# zero_board.net
KiCad netlist of a schematic drawn in EAGLE
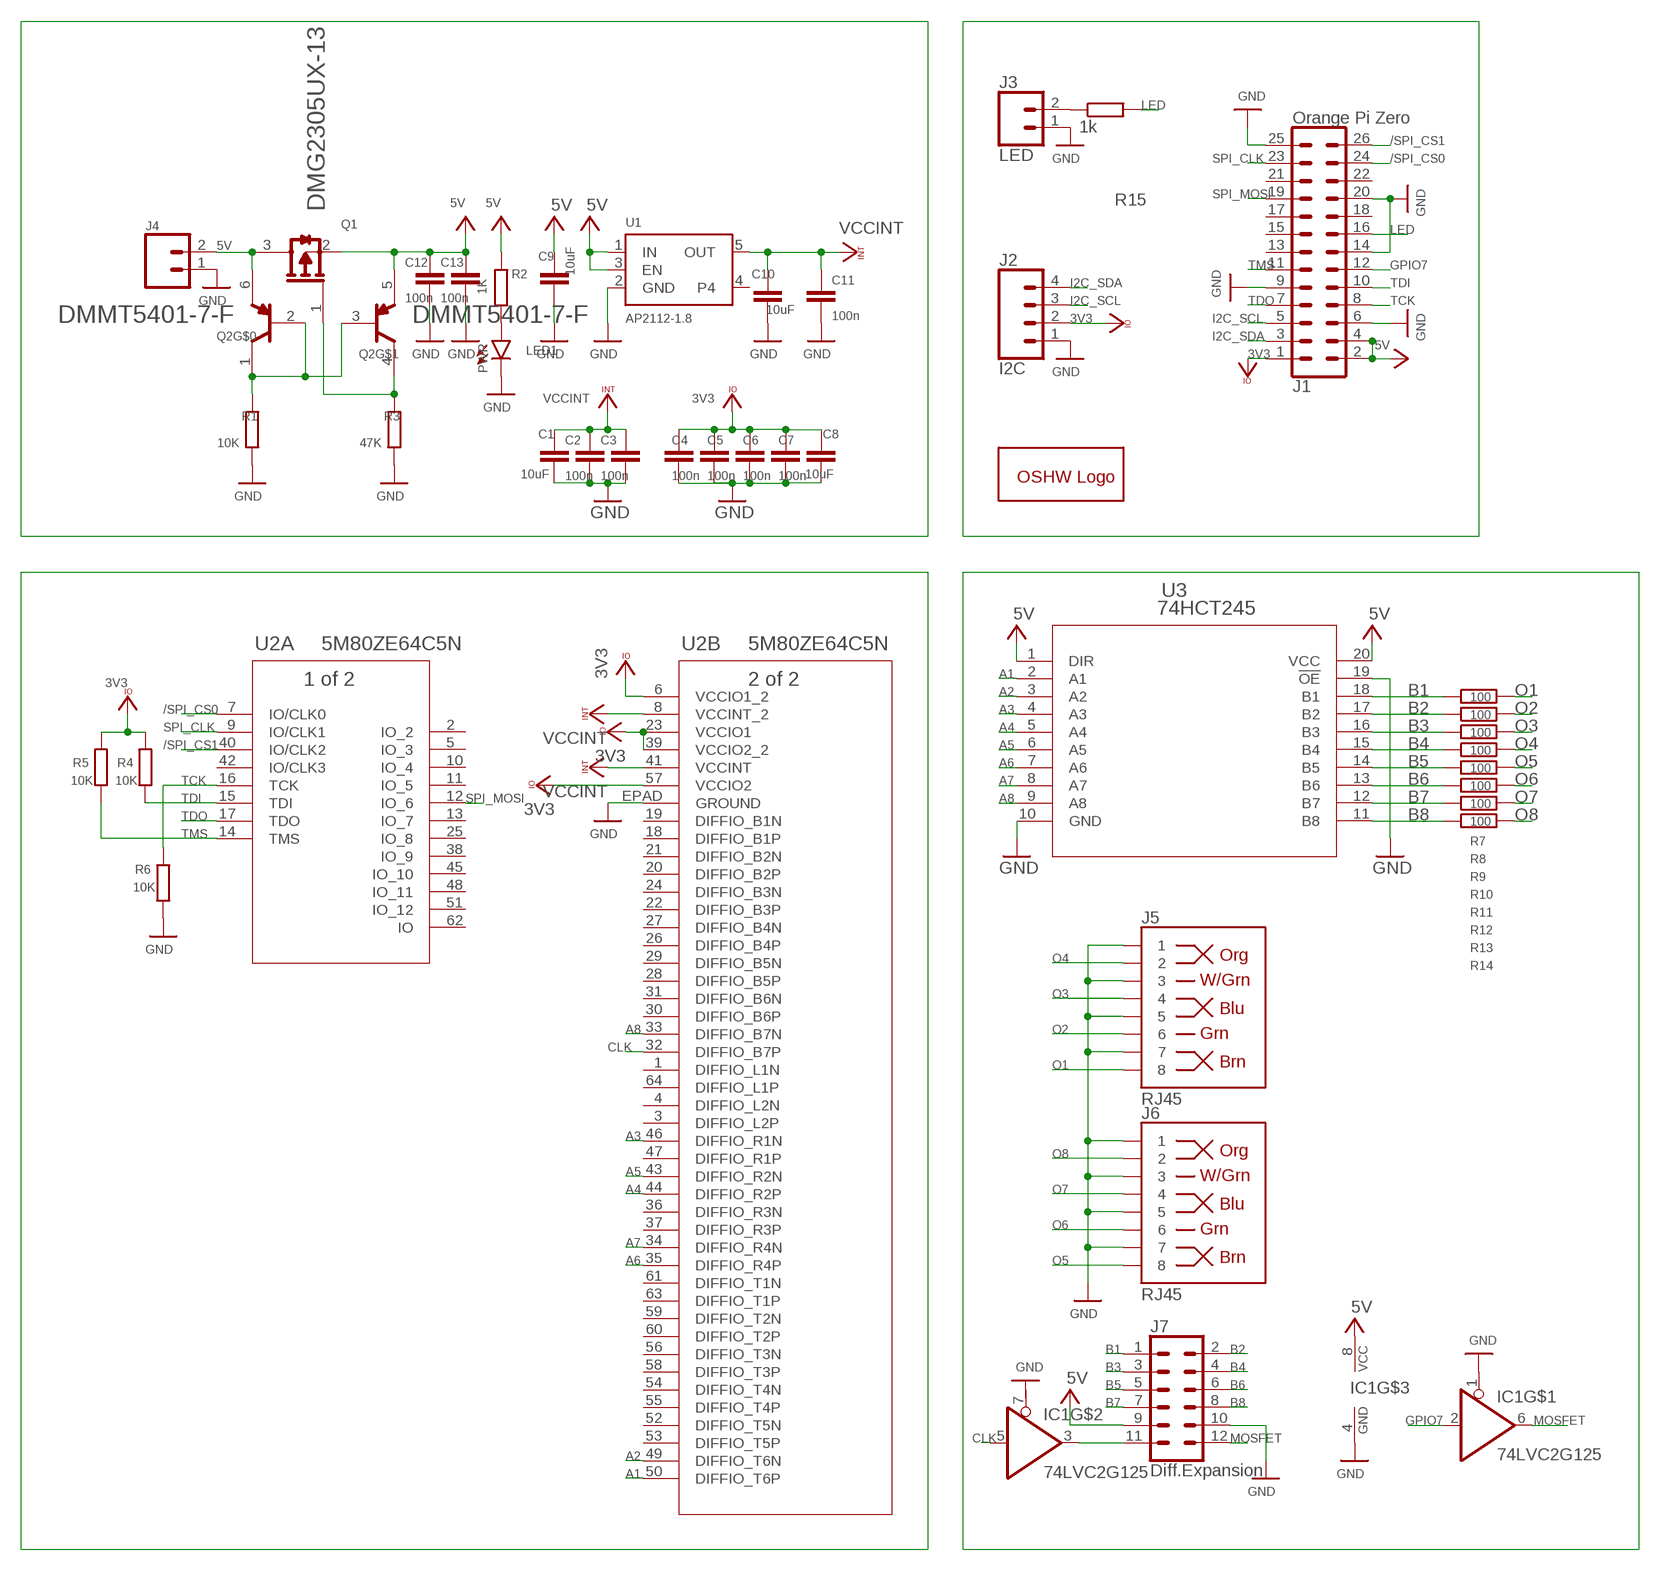
[diagram p0: schematic, sheet 1]

(export (version "E")
  (design (tool "Eeschema 10.0.6"))
  (components
    (comp (ref "C1")
      (value "10uF")
      (footprint "eagle-import:C0805")
      (libsource (lib "eagle-import") (part "C-EUC0805"))
    )
    (comp (ref "C2")
      (value "100n")
      (footprint "eagle-import:C0603")
      (libsource (lib "eagle-import") (part "C-EUC0603"))
    )
    (comp (ref "C3")
      (value "100n")
      (footprint "eagle-import:C0603")
      (libsource (lib "eagle-import") (part "C-EUC0603"))
    )
    (comp (ref "C4")
      (value "100n")
      (footprint "eagle-import:C0603")
      (libsource (lib "eagle-import") (part "C-EUC0603"))
    )
    (comp (ref "C5")
      (value "100n")
      (footprint "eagle-import:C0603")
      (libsource (lib "eagle-import") (part "C-EUC0603"))
    )
    (comp (ref "C6")
      (value "100n")
      (footprint "eagle-import:C0603")
      (libsource (lib "eagle-import") (part "C-EUC0603"))
    )
    (comp (ref "C7")
      (value "100n")
      (footprint "eagle-import:C0603")
      (libsource (lib "eagle-import") (part "C-EUC0603"))
    )
    (comp (ref "C8")
      (value "10uF")
      (footprint "eagle-import:C0805")
      (libsource (lib "eagle-import") (part "C-EUC0805"))
    )
    (comp (ref "C9")
      (value "10uF")
      (footprint "eagle-import:C0805")
      (libsource (lib "eagle-import") (part "C-EUC0805"))
    )
    (comp (ref "C10")
      (value "10uF")
      (footprint "eagle-import:C0805")
      (libsource (lib "eagle-import") (part "C-EUC0805"))
    )
    (comp (ref "C11")
      (value "100n")
      (footprint "eagle-import:C0603")
      (libsource (lib "eagle-import") (part "C-EUC0603"))
    )
    (comp (ref "C12")
      (value "100n")
      (footprint "eagle-import:C0603")
      (libsource (lib "eagle-import") (part "C-EUC0603"))
    )
    (comp (ref "C13")
      (value "100n")
      (footprint "eagle-import:C0603")
      (libsource (lib "eagle-import") (part "C-EUC0603"))
    )
    (comp (ref "GOLD_ORB_SM1")
      (value "OSHWLOGOLOGO5MM")
      (footprint "eagle-import:OSHW_5MM")
      (libsource (lib "eagle-import") (part "OSHWLOGOLOGO5MM"))
    )
    (comp (ref "IC1")
      (value "74LVC2G125")
      (footprint "eagle-import:SSOP08")
      (libsource (lib "eagle-import") (part "742G125DCTLVC"))
    )
    (comp (ref "J1")
      (value "Orange Pi Zero")
      (footprint "eagle-import:2X13")
      (libsource (lib "eagle-import") (part "CONN_13X22X13"))
    )
    (comp (ref "J2")
      (value "I2C")
      (footprint "eagle-import:1X04")
      (libsource (lib "eagle-import") (part "CONN_04"))
    )
    (comp (ref "J3")
      (value "LED")
      (footprint "eagle-import:1X02")
      (libsource (lib "eagle-import") (part "SparkFun-Connectors_513_CONN_02"))
    )
    (comp (ref "J4")
      (value "5V")
      (footprint "eagle-import:SCREWTERMINAL-3.5MM-2")
      (libsource (lib "eagle-import") (part "CONN_023.5MM"))
    )
    (comp (ref "J5")
      (value "RJ45")
      (footprint "eagle-import:RJ45-8")
      (libsource (lib "eagle-import") (part "RJ45-8"))
    )
    (comp (ref "J6")
      (value "RJ45")
      (footprint "eagle-import:RJ45-8")
      (libsource (lib "eagle-import") (part "RJ45-8"))
    )
    (comp (ref "J7")
      (value "Diff.Expansion")
      (footprint "eagle-import:2X6")
      (libsource (lib "eagle-import") (part "CONN_06X2PTH_FEMALE"))
    )
    (comp (ref "LED1")
      (value "PWR")
      (footprint "eagle-import:CHIP-LED0603")
      (libsource (lib "eagle-import") (part "LEDCHIP-LED0603"))
    )
    (comp (ref "Q1")
      (value "DIODES_INC._DMG2305UX-13DIODES_INC._DMG2305UX-13_0_0")
      (footprint "eagle-import:DIODES_INC._DMG2305UX-13_0")
      (fields
        (field (name "DIGIKEY_PART_NUMBER") "DMG2305UX-13DICT-ND")
        (field (name "MF") "Diodes Inc.")
        (field (name "MOUSER_PART_NUMBER") "621-DMG2305UX-13")
      )
      (libsource (lib "eagle-import") (part "DIODES_INC._DMG2305UX-13DIODES_INC._DMG2305UX-13_0_0"))
    )
    (comp (ref "Q2")
      (value "DMMT5401-7-F_0_0")
      (footprint "eagle-import:DIODES_DMMT5401-7-F_0")
      (fields
        (field (name "DIGIKEY_PART_NUMBER") "DMMT5401-FDICT-ND")
        (field (name "MF") "Diodes")
        (field (name "MOUSER_PART_NUMBER") "621-DMMT5401-7-F")
      )
      (libsource (lib "eagle-import") (part "DIODES_DMMT5401-7-FDIODES_DMMT5401-7-F_0_0"))
    )
    (comp (ref "R1")
      (value "10K")
      (footprint "eagle-import:R0402")
      (libsource (lib "eagle-import") (part "R-EU_R0402"))
    )
    (comp (ref "R2")
      (value "1K")
      (footprint "eagle-import:R0402")
      (libsource (lib "eagle-import") (part "resistor_348_R-EU_R0402"))
    )
    (comp (ref "R3")
      (value "47K")
      (footprint "eagle-import:R0402")
      (libsource (lib "eagle-import") (part "R-EU_R0402"))
    )
    (comp (ref "R4")
      (value "10K")
      (footprint "eagle-import:R0402")
      (libsource (lib "eagle-import") (part "R-EU_R0402"))
    )
    (comp (ref "R5")
      (value "10K")
      (footprint "eagle-import:R0402")
      (libsource (lib "eagle-import") (part "R-EU_R0402"))
    )
    (comp (ref "R6")
      (value "10K")
      (footprint "eagle-import:R0402")
      (libsource (lib "eagle-import") (part "R-EU_R0402"))
    )
    (comp (ref "R7")
      (value "100")
      (footprint "eagle-import:R0402")
      (libsource (lib "eagle-import") (part "R-EU_R0402"))
    )
    (comp (ref "R8")
      (value "100")
      (footprint "eagle-import:R0402")
      (libsource (lib "eagle-import") (part "R-EU_R0402"))
    )
    (comp (ref "R9")
      (value "100")
      (footprint "eagle-import:R0402")
      (libsource (lib "eagle-import") (part "R-EU_R0402"))
    )
    (comp (ref "R10")
      (value "100")
      (footprint "eagle-import:R0402")
      (libsource (lib "eagle-import") (part "R-EU_R0402"))
    )
    (comp (ref "R11")
      (value "100")
      (footprint "eagle-import:R0402")
      (libsource (lib "eagle-import") (part "R-EU_R0402"))
    )
    (comp (ref "R12")
      (value "100")
      (footprint "eagle-import:R0402")
      (libsource (lib "eagle-import") (part "R-EU_R0402"))
    )
    (comp (ref "R13")
      (value "100")
      (footprint "eagle-import:R0402")
      (libsource (lib "eagle-import") (part "R-EU_R0402"))
    )
    (comp (ref "R14")
      (value "100")
      (footprint "eagle-import:R0402")
      (libsource (lib "eagle-import") (part "R-EU_R0402"))
    )
    (comp (ref "R15")
      (value "1k")
      (footprint "eagle-import:R0402")
      (libsource (lib "eagle-import") (part "R-EU_R0402"))
    )
    (comp (ref "U1")
      (value "AP2112-1.8")
      (footprint "eagle-import:SOT23-5")
      (libsource (lib "eagle-import") (part "VREG_SOT23-5"))
    )
    (comp (ref "U2")
      (value "5M80ZE64C5N")
      (footprint "eagle-import:EQFP64P_A1P2-D4P5_INT-L")
      (fields (field (name "COPYRIGHT") "Copyright (C) 2018 Accelerated Designs. All rights reserved"))
      (libsource (lib "eagle-import") (part "5M80ZE64C5NEQFP64P_A1P2-D4P5_INT-L"))
    )
    (comp (ref "U3")
      (value "74HCT245")
      (footprint "eagle-import:PW20")
      (fields
        (field (name "GENERIC_PART_NUMBER") "SN74HCT245")
        (field (name "MANUFACTURER") "Texas Instruments")
        (field (name "MANUFACTURER_PART_NUMBER") "SN74HCT245PWR")
      )
      (libsource (lib "eagle-import") (part "SN74HCT245PWR"))
    )
  )
  (nets
    (net (code "1") (name "/A1") (class "Default")
      (node (ref "U2") (pin "50") (pinfunction "DIFFIO_T6P_50") (pintype "bidirectional"))
      (node (ref "U3") (pin "2") (pinfunction "A1_2") (pintype "bidirectional"))
    )
    (net (code "2") (name "/A2") (class "Default")
      (node (ref "U2") (pin "49") (pinfunction "DIFFIO_T6N_49") (pintype "bidirectional"))
      (node (ref "U3") (pin "3") (pinfunction "A2_3") (pintype "bidirectional"))
    )
    (net (code "3") (name "/A3") (class "Default")
      (node (ref "U2") (pin "46") (pinfunction "DIFFIO_R1N_46") (pintype "bidirectional"))
      (node (ref "U3") (pin "4") (pinfunction "A3_4") (pintype "bidirectional"))
    )
    (net (code "4") (name "/A4") (class "Default")
      (node (ref "U2") (pin "44") (pinfunction "DIFFIO_R2P_44") (pintype "bidirectional"))
      (node (ref "U3") (pin "5") (pinfunction "A4_5") (pintype "bidirectional"))
    )
    (net (code "5") (name "/A5") (class "Default")
      (node (ref "U2") (pin "43") (pinfunction "DIFFIO_R2N_43") (pintype "bidirectional"))
      (node (ref "U3") (pin "6") (pinfunction "A5_6") (pintype "bidirectional"))
    )
    (net (code "6") (name "/A6") (class "Default")
      (node (ref "U2") (pin "35") (pinfunction "DIFFIO_R4P_35") (pintype "bidirectional"))
      (node (ref "U3") (pin "7") (pinfunction "A6_7") (pintype "bidirectional"))
    )
    (net (code "7") (name "/A7") (class "Default")
      (node (ref "U2") (pin "34") (pinfunction "DIFFIO_R4N_34") (pintype "bidirectional"))
      (node (ref "U3") (pin "8") (pinfunction "A7_8") (pintype "bidirectional"))
    )
    (net (code "8") (name "/A8") (class "Default")
      (node (ref "U2") (pin "33") (pinfunction "DIFFIO_B7N_33") (pintype "bidirectional"))
      (node (ref "U3") (pin "9") (pinfunction "A8_9") (pintype "bidirectional"))
    )
    (net (code "9") (name "/B1") (class "Default")
      (node (ref "J7") (pin "1") (pinfunction "1_1") (pintype "passive"))
      (node (ref "R7") (pin "1") (pinfunction "1_1") (pintype "passive"))
      (node (ref "U3") (pin "18") (pinfunction "B1_18") (pintype "bidirectional"))
    )
    (net (code "10") (name "/B2") (class "Default")
      (node (ref "J7") (pin "2") (pinfunction "2_2") (pintype "passive"))
      (node (ref "R8") (pin "1") (pinfunction "1_1") (pintype "passive"))
      (node (ref "U3") (pin "17") (pinfunction "B2_17") (pintype "bidirectional"))
    )
    (net (code "11") (name "/B3") (class "Default")
      (node (ref "J7") (pin "3") (pinfunction "3_3") (pintype "passive"))
      (node (ref "R9") (pin "1") (pinfunction "1_1") (pintype "passive"))
      (node (ref "U3") (pin "16") (pinfunction "B3_16") (pintype "bidirectional"))
    )
    (net (code "12") (name "/B4") (class "Default")
      (node (ref "J7") (pin "4") (pinfunction "4_4") (pintype "passive"))
      (node (ref "R10") (pin "1") (pinfunction "1_1") (pintype "passive"))
      (node (ref "U3") (pin "15") (pinfunction "B4_15") (pintype "bidirectional"))
    )
    (net (code "13") (name "/B5") (class "Default")
      (node (ref "J7") (pin "5") (pinfunction "5_5") (pintype "passive"))
      (node (ref "R11") (pin "1") (pinfunction "1_1") (pintype "passive"))
      (node (ref "U3") (pin "14") (pinfunction "B5_14") (pintype "bidirectional"))
    )
    (net (code "14") (name "/B6") (class "Default")
      (node (ref "J7") (pin "6") (pinfunction "6_6") (pintype "passive"))
      (node (ref "R12") (pin "1") (pinfunction "1_1") (pintype "passive"))
      (node (ref "U3") (pin "13") (pinfunction "B6_13") (pintype "bidirectional"))
    )
    (net (code "15") (name "/B7") (class "Default")
      (node (ref "J7") (pin "7") (pinfunction "7_7") (pintype "passive"))
      (node (ref "R13") (pin "1") (pinfunction "1_1") (pintype "passive"))
      (node (ref "U3") (pin "12") (pinfunction "B7_12") (pintype "bidirectional"))
    )
    (net (code "16") (name "/B8") (class "Default")
      (node (ref "J7") (pin "8") (pinfunction "8_8") (pintype "passive"))
      (node (ref "R14") (pin "1") (pinfunction "1_1") (pintype "passive"))
      (node (ref "U3") (pin "11") (pinfunction "B8_11") (pintype "bidirectional"))
    )
    (net (code "17") (name "/CLK") (class "Default")
      (node (ref "IC1") (pin "5") (pinfunction "I_5") (pintype "input"))
      (node (ref "U2") (pin "32") (pinfunction "DIFFIO_B7P_32") (pintype "bidirectional"))
    )
    (net (code "18") (name "/GPIO7") (class "Default")
      (node (ref "IC1") (pin "2") (pinfunction "I_2") (pintype "input"))
      (node (ref "J1") (pin "12") (pinfunction "12_12") (pintype "passive"))
    )
    (net (code "19") (name "/I2C_SCL") (class "Default")
      (node (ref "J1") (pin "5") (pinfunction "5_5") (pintype "passive"))
      (node (ref "J2") (pin "3") (pinfunction "3_3") (pintype "passive"))
    )
    (net (code "20") (name "/I2C_SDA") (class "Default")
      (node (ref "J1") (pin "3") (pinfunction "3_3") (pintype "passive"))
      (node (ref "J2") (pin "4") (pinfunction "4_4") (pintype "passive"))
    )
    (net (code "21") (name "/LED") (class "Default")
      (node (ref "J1") (pin "16") (pinfunction "16_16") (pintype "passive"))
      (node (ref "R15") (pin "2") (pinfunction "2_2") (pintype "passive"))
    )
    (net (code "22") (name "/MOSFET") (class "Default")
      (node (ref "IC1") (pin "6") (pinfunction "O_6") (pintype "tri_state"))
      (node (ref "J7") (pin "12") (pinfunction "12_12") (pintype "passive"))
    )
    (net (code "23") (name "/O1") (class "Default")
      (node (ref "J5") (pin "8") (pinfunction "8_8") (pintype "bidirectional"))
      (node (ref "R7") (pin "2") (pinfunction "2_2") (pintype "passive"))
    )
    (net (code "24") (name "/O2") (class "Default")
      (node (ref "J5") (pin "6") (pinfunction "6_6") (pintype "bidirectional"))
      (node (ref "R8") (pin "2") (pinfunction "2_2") (pintype "passive"))
    )
    (net (code "25") (name "/O3") (class "Default")
      (node (ref "J5") (pin "4") (pinfunction "4_4") (pintype "bidirectional"))
      (node (ref "R9") (pin "2") (pinfunction "2_2") (pintype "passive"))
    )
    (net (code "26") (name "/O4") (class "Default")
      (node (ref "J5") (pin "2") (pinfunction "2_2") (pintype "bidirectional"))
      (node (ref "R10") (pin "2") (pinfunction "2_2") (pintype "passive"))
    )
    (net (code "27") (name "/O5") (class "Default")
      (node (ref "J6") (pin "8") (pinfunction "8_8") (pintype "bidirectional"))
      (node (ref "R11") (pin "2") (pinfunction "2_2") (pintype "passive"))
    )
    (net (code "28") (name "/O6") (class "Default")
      (node (ref "J6") (pin "6") (pinfunction "6_6") (pintype "bidirectional"))
      (node (ref "R12") (pin "2") (pinfunction "2_2") (pintype "passive"))
    )
    (net (code "29") (name "/O7") (class "Default")
      (node (ref "J6") (pin "4") (pinfunction "4_4") (pintype "bidirectional"))
      (node (ref "R13") (pin "2") (pinfunction "2_2") (pintype "passive"))
    )
    (net (code "30") (name "/O8") (class "Default")
      (node (ref "J6") (pin "2") (pinfunction "2_2") (pintype "bidirectional"))
      (node (ref "R14") (pin "2") (pinfunction "2_2") (pintype "passive"))
    )
    (net (code "31") (name "/SPI_CLK") (class "Default")
      (node (ref "J1") (pin "23") (pinfunction "23_23") (pintype "passive"))
      (node (ref "U2") (pin "9") (pinfunction "IO/CLK1_9") (pintype "bidirectional"))
    )
    (net (code "32") (name "/SPI_MOSI") (class "Default")
      (node (ref "J1") (pin "19") (pinfunction "19_19") (pintype "passive"))
      (node (ref "U2") (pin "12") (pinfunction "IO_6_12") (pintype "bidirectional"))
    )
    (net (code "33") (name "/TCK") (class "Default")
      (node (ref "J1") (pin "8") (pinfunction "8_8") (pintype "passive"))
      (node (ref "R6") (pin "2") (pinfunction "2_2") (pintype "passive"))
      (node (ref "U2") (pin "16") (pinfunction "TCK_16") (pintype "passive"))
    )
    (net (code "34") (name "/TDI") (class "Default")
      (node (ref "J1") (pin "10") (pinfunction "10_10") (pintype "passive"))
      (node (ref "R4") (pin "1") (pinfunction "1_1") (pintype "passive"))
      (node (ref "U2") (pin "15") (pinfunction "TDI_15") (pintype "passive"))
    )
    (net (code "35") (name "/TDO") (class "Default")
      (node (ref "J1") (pin "7") (pinfunction "7_7") (pintype "passive"))
      (node (ref "U2") (pin "17") (pinfunction "TDO_17") (pintype "passive"))
    )
    (net (code "36") (name "/TMS") (class "Default")
      (node (ref "J1") (pin "11") (pinfunction "11_11") (pintype "passive"))
      (node (ref "R5") (pin "1") (pinfunction "1_1") (pintype "passive"))
      (node (ref "U2") (pin "14") (pinfunction "TMS_14") (pintype "passive"))
    )
    (net (code "37") (name "/{slash}SPI_CS0") (class "Default")
      (node (ref "J1") (pin "24") (pinfunction "24_24") (pintype "passive"))
      (node (ref "U2") (pin "7") (pinfunction "IO/CLK0_7") (pintype "bidirectional"))
    )
    (net (code "38") (name "/{slash}SPI_CS1") (class "Default")
      (node (ref "J1") (pin "26") (pinfunction "26_26") (pintype "passive"))
      (node (ref "U2") (pin "40") (pinfunction "IO/CLK2_40") (pintype "bidirectional"))
    )
    (net (code "39") (name "3V3") (class "Default")
      (node (ref "C4") (pin "1") (pinfunction "1_1") (pintype "passive"))
      (node (ref "C5") (pin "1") (pinfunction "1_1") (pintype "passive"))
      (node (ref "C6") (pin "1") (pinfunction "1_1") (pintype "passive"))
      (node (ref "C7") (pin "1") (pinfunction "1_1") (pintype "passive"))
      (node (ref "C8") (pin "1") (pinfunction "1_1") (pintype "passive"))
      (node (ref "J1") (pin "1") (pinfunction "1_1") (pintype "passive"))
      (node (ref "J2") (pin "2") (pinfunction "2_2") (pintype "passive"))
      (node (ref "R4") (pin "2") (pinfunction "2_2") (pintype "passive"))
      (node (ref "R5") (pin "2") (pinfunction "2_2") (pintype "passive"))
      (node (ref "U2") (pin "23") (pinfunction "VCCIO1_23") (pintype "power_in"))
      (node (ref "U2") (pin "39") (pinfunction "VCCIO2_2_39") (pintype "power_in"))
      (node (ref "U2") (pin "57") (pinfunction "VCCIO2_57") (pintype "power_in"))
      (node (ref "U2") (pin "6") (pinfunction "VCCIO1_2_6") (pintype "power_in"))
    )
    (net (code "40") (name "5V") (class "Default")
      (node (ref "C12") (pin "1") (pinfunction "1_1") (pintype "passive"))
      (node (ref "C13") (pin "1") (pinfunction "1_1") (pintype "passive"))
      (node (ref "C9") (pin "1") (pinfunction "1_1") (pintype "passive"))
      (node (ref "IC1") (pin "8") (pinfunction "VCC_8") (pintype "power_in"))
      (node (ref "J1") (pin "2") (pinfunction "2_2") (pintype "passive"))
      (node (ref "J1") (pin "4") (pinfunction "4_4") (pintype "passive"))
      (node (ref "J7") (pin "9") (pinfunction "9_9") (pintype "passive"))
      (node (ref "Q1") (pin "2") (pinfunction "S_2") (pintype "passive"))
      (node (ref "Q2") (pin "5") (pinfunction "E2_5") (pintype "passive"))
      (node (ref "R2") (pin "1") (pinfunction "1_1") (pintype "passive"))
      (node (ref "U1") (pin "1") (pinfunction "IN_1") (pintype "power_in"))
      (node (ref "U1") (pin "3") (pinfunction "EN_3") (pintype "input"))
      (node (ref "U3") (pin "1") (pinfunction "DIR_1") (pintype "input"))
      (node (ref "U3") (pin "20") (pinfunction "VCC_20") (pintype "power_in"))
    )
    (net (code "41") (name "GND") (class "Default")
      (node (ref "C1") (pin "2") (pinfunction "2_2") (pintype "passive"))
      (node (ref "C10") (pin "2") (pinfunction "2_2") (pintype "passive"))
      (node (ref "C11") (pin "2") (pinfunction "2_2") (pintype "passive"))
      (node (ref "C12") (pin "2") (pinfunction "2_2") (pintype "passive"))
      (node (ref "C13") (pin "2") (pinfunction "2_2") (pintype "passive"))
      (node (ref "C2") (pin "2") (pinfunction "2_2") (pintype "passive"))
      (node (ref "C3") (pin "2") (pinfunction "2_2") (pintype "passive"))
      (node (ref "C4") (pin "2") (pinfunction "2_2") (pintype "passive"))
      (node (ref "C5") (pin "2") (pinfunction "2_2") (pintype "passive"))
      (node (ref "C6") (pin "2") (pinfunction "2_2") (pintype "passive"))
      (node (ref "C7") (pin "2") (pinfunction "2_2") (pintype "passive"))
      (node (ref "C8") (pin "2") (pinfunction "2_2") (pintype "passive"))
      (node (ref "C9") (pin "2") (pinfunction "2_2") (pintype "passive"))
      (node (ref "IC1") (pin "1") (pinfunction "OE_1") (pintype "input"))
      (node (ref "IC1") (pin "4") (pinfunction "GND_4") (pintype "power_in"))
      (node (ref "J1") (pin "14") (pinfunction "14_14") (pintype "passive"))
      (node (ref "J1") (pin "20") (pinfunction "20_20") (pintype "passive"))
      (node (ref "J1") (pin "25") (pinfunction "25_25") (pintype "passive"))
      (node (ref "J1") (pin "6") (pinfunction "6_6") (pintype "passive"))
      (node (ref "J1") (pin "9") (pinfunction "9_9") (pintype "passive"))
      (node (ref "J2") (pin "1") (pinfunction "1_1") (pintype "passive"))
      (node (ref "J3") (pin "1") (pinfunction "1_1") (pintype "passive"))
      (node (ref "J4") (pin "1") (pinfunction "1_1") (pintype "passive"))
      (node (ref "J5") (pin "1") (pinfunction "1_1") (pintype "bidirectional"))
      (node (ref "J5") (pin "3") (pinfunction "3_3") (pintype "bidirectional"))
      (node (ref "J5") (pin "5") (pinfunction "5_5") (pintype "bidirectional"))
      (node (ref "J5") (pin "7") (pinfunction "7_7") (pintype "bidirectional"))
      (node (ref "J6") (pin "1") (pinfunction "1_1") (pintype "bidirectional"))
      (node (ref "J6") (pin "3") (pinfunction "3_3") (pintype "bidirectional"))
      (node (ref "J6") (pin "5") (pinfunction "5_5") (pintype "bidirectional"))
      (node (ref "J6") (pin "7") (pinfunction "7_7") (pintype "bidirectional"))
      (node (ref "J7") (pin "10") (pinfunction "10_10") (pintype "passive"))
      (node (ref "LED1") (pin "C") (pinfunction "C_C") (pintype "passive"))
      (node (ref "R1") (pin "1") (pinfunction "1_1") (pintype "passive"))
      (node (ref "R3") (pin "1") (pinfunction "1_1") (pintype "passive"))
      (node (ref "R6") (pin "1") (pinfunction "1_1") (pintype "passive"))
      (node (ref "U1") (pin "2") (pinfunction "GND_2") (pintype "power_in"))
      (node (ref "U2") (pin "EPAD") (pinfunction "GROUND_EPAD") (pintype "passive"))
      (node (ref "U3") (pin "10") (pinfunction "GND_10") (pintype "power_in"))
      (node (ref "U3") (pin "19") (pinfunction "~{OE}_19") (pintype "input"))
    )
    (net (code "42") (name "Net-(IC1B-O)") (class "Default")
      (node (ref "IC1") (pin "3") (pinfunction "O_3") (pintype "tri_state"))
      (node (ref "J7") (pin "11") (pinfunction "11_11") (pintype "passive"))
    )
    (net (code "43") (name "Net-(J3-Pad2)") (class "Default")
      (node (ref "J3") (pin "2") (pinfunction "2_2") (pintype "passive"))
      (node (ref "R15") (pin "1") (pinfunction "1_1") (pintype "passive"))
    )
    (net (code "44") (name "Net-(LED1-PadA)") (class "Default")
      (node (ref "LED1") (pin "A") (pinfunction "A_A") (pintype "passive"))
      (node (ref "R2") (pin "2") (pinfunction "2_2") (pintype "passive"))
    )
    (net (code "45") (name "Net-(Q1-D)") (class "Default")
      (node (ref "J4") (pin "2") (pinfunction "2_2") (pintype "passive"))
      (node (ref "Q1") (pin "3") (pinfunction "D_3") (pintype "passive"))
      (node (ref "Q2") (pin "6") (pinfunction "E1_6") (pintype "passive"))
    )
    (net (code "46") (name "Net-(Q1-G)") (class "Default")
      (node (ref "Q1") (pin "1") (pinfunction "G_1") (pintype "passive"))
      (node (ref "Q2") (pin "4") (pinfunction "C2_4") (pintype "passive"))
      (node (ref "R3") (pin "2") (pinfunction "2_2") (pintype "passive"))
    )
    (net (code "47") (name "Net-(Q2A-B1)") (class "Default")
      (node (ref "Q2") (pin "1") (pinfunction "C1_1") (pintype "passive"))
      (node (ref "Q2") (pin "2") (pinfunction "B1_2") (pintype "passive"))
      (node (ref "Q2") (pin "3") (pinfunction "B2_3") (pintype "passive"))
      (node (ref "R1") (pin "2") (pinfunction "2_2") (pintype "passive"))
    )
    (net (code "48") (name "VCCINT") (class "Default")
      (node (ref "C1") (pin "1") (pinfunction "1_1") (pintype "passive"))
      (node (ref "C10") (pin "1") (pinfunction "1_1") (pintype "passive"))
      (node (ref "C11") (pin "1") (pinfunction "1_1") (pintype "passive"))
      (node (ref "C2") (pin "1") (pinfunction "1_1") (pintype "passive"))
      (node (ref "C3") (pin "1") (pinfunction "1_1") (pintype "passive"))
      (node (ref "U1") (pin "5") (pinfunction "OUT_5") (pintype "power_in"))
      (node (ref "U2") (pin "41") (pinfunction "VCCINT_41") (pintype "power_in"))
      (node (ref "U2") (pin "8") (pinfunction "VCCINT_2_8") (pintype "power_in"))
    )
    (net (code "49") (name "unconnected-(IC1B-OE-Pad7)") (class "Default")
      (node (ref "IC1") (pin "7") (pinfunction "OE_7") (pintype "input"))
    )
    (net (code "50") (name "unconnected-(J1-Pad13)") (class "Default")
      (node (ref "J1") (pin "13") (pinfunction "13_13") (pintype "passive"))
    )
    (net (code "51") (name "unconnected-(J1-Pad15)") (class "Default")
      (node (ref "J1") (pin "15") (pinfunction "15_15") (pintype "passive"))
    )
    (net (code "52") (name "unconnected-(J1-Pad17)") (class "Default")
      (node (ref "J1") (pin "17") (pinfunction "17_17") (pintype "passive"))
    )
    (net (code "53") (name "unconnected-(J1-Pad18)") (class "Default")
      (node (ref "J1") (pin "18") (pinfunction "18_18") (pintype "passive"))
    )
    (net (code "54") (name "unconnected-(J1-Pad21)") (class "Default")
      (node (ref "J1") (pin "21") (pinfunction "21_21") (pintype "passive"))
    )
    (net (code "55") (name "unconnected-(J1-Pad22)") (class "Default")
      (node (ref "J1") (pin "22") (pinfunction "22_22") (pintype "passive"))
    )
    (net (code "56") (name "unconnected-(U1-P4-Pad4)") (class "Default")
      (node (ref "U1") (pin "4") (pinfunction "P4_4") (pintype "bidirectional"))
    )
    (net (code "57") (name "unconnected-(U2A-IO-Pad62)") (class "Default")
      (node (ref "U2") (pin "62") (pinfunction "IO_62") (pintype "bidirectional"))
    )
    (net (code "58") (name "unconnected-(U2A-IO_2-Pad2)") (class "Default")
      (node (ref "U2") (pin "2") (pinfunction "IO_2_2") (pintype "bidirectional"))
    )
    (net (code "59") (name "unconnected-(U2A-IO_3-Pad5)") (class "Default")
      (node (ref "U2") (pin "5") (pinfunction "IO_3_5") (pintype "bidirectional"))
    )
    (net (code "60") (name "unconnected-(U2A-IO_4-Pad10)") (class "Default")
      (node (ref "U2") (pin "10") (pinfunction "IO_4_10") (pintype "bidirectional"))
    )
    (net (code "61") (name "unconnected-(U2A-IO_5-Pad11)") (class "Default")
      (node (ref "U2") (pin "11") (pinfunction "IO_5_11") (pintype "bidirectional"))
    )
    (net (code "62") (name "unconnected-(U2A-IO_7-Pad13)") (class "Default")
      (node (ref "U2") (pin "13") (pinfunction "IO_7_13") (pintype "bidirectional"))
    )
    (net (code "63") (name "unconnected-(U2A-IO_8-Pad25)") (class "Default")
      (node (ref "U2") (pin "25") (pinfunction "IO_8_25") (pintype "bidirectional"))
    )
    (net (code "64") (name "unconnected-(U2A-IO_9-Pad38)") (class "Default")
      (node (ref "U2") (pin "38") (pinfunction "IO_9_38") (pintype "bidirectional"))
    )
    (net (code "65") (name "unconnected-(U2A-IO_10-Pad45)") (class "Default")
      (node (ref "U2") (pin "45") (pinfunction "IO_10_45") (pintype "bidirectional"))
    )
    (net (code "66") (name "unconnected-(U2A-IO_11-Pad48)") (class "Default")
      (node (ref "U2") (pin "48") (pinfunction "IO_11_48") (pintype "bidirectional"))
    )
    (net (code "67") (name "unconnected-(U2A-IO_12-Pad51)") (class "Default")
      (node (ref "U2") (pin "51") (pinfunction "IO_12_51") (pintype "bidirectional"))
    )
    (net (code "68") (name "unconnected-(U2A-IO{slash}CLK3-Pad42)") (class "Default")
      (node (ref "U2") (pin "42") (pinfunction "IO/CLK3_42") (pintype "bidirectional"))
    )
    (net (code "69") (name "unconnected-(U2B-DIFFIO_B1N-Pad19)") (class "Default")
      (node (ref "U2") (pin "19") (pinfunction "DIFFIO_B1N_19") (pintype "bidirectional"))
    )
    (net (code "70") (name "unconnected-(U2B-DIFFIO_B1P-Pad18)") (class "Default")
      (node (ref "U2") (pin "18") (pinfunction "DIFFIO_B1P_18") (pintype "bidirectional"))
    )
    (net (code "71") (name "unconnected-(U2B-DIFFIO_B2N-Pad21)") (class "Default")
      (node (ref "U2") (pin "21") (pinfunction "DIFFIO_B2N_21") (pintype "bidirectional"))
    )
    (net (code "72") (name "unconnected-(U2B-DIFFIO_B2P-Pad20)") (class "Default")
      (node (ref "U2") (pin "20") (pinfunction "DIFFIO_B2P_20") (pintype "bidirectional"))
    )
    (net (code "73") (name "unconnected-(U2B-DIFFIO_B3N-Pad24)") (class "Default")
      (node (ref "U2") (pin "24") (pinfunction "DIFFIO_B3N_24") (pintype "bidirectional"))
    )
    (net (code "74") (name "unconnected-(U2B-DIFFIO_B3P-Pad22)") (class "Default")
      (node (ref "U2") (pin "22") (pinfunction "DIFFIO_B3P_22") (pintype "bidirectional"))
    )
    (net (code "75") (name "unconnected-(U2B-DIFFIO_B4N-Pad27)") (class "Default")
      (node (ref "U2") (pin "27") (pinfunction "DIFFIO_B4N_27") (pintype "bidirectional"))
    )
    (net (code "76") (name "unconnected-(U2B-DIFFIO_B4P-Pad26)") (class "Default")
      (node (ref "U2") (pin "26") (pinfunction "DIFFIO_B4P_26") (pintype "bidirectional"))
    )
    (net (code "77") (name "unconnected-(U2B-DIFFIO_B5N-Pad29)") (class "Default")
      (node (ref "U2") (pin "29") (pinfunction "DIFFIO_B5N_29") (pintype "bidirectional"))
    )
    (net (code "78") (name "unconnected-(U2B-DIFFIO_B5P-Pad28)") (class "Default")
      (node (ref "U2") (pin "28") (pinfunction "DIFFIO_B5P_28") (pintype "bidirectional"))
    )
    (net (code "79") (name "unconnected-(U2B-DIFFIO_B6N-Pad31)") (class "Default")
      (node (ref "U2") (pin "31") (pinfunction "DIFFIO_B6N_31") (pintype "bidirectional"))
    )
    (net (code "80") (name "unconnected-(U2B-DIFFIO_B6P-Pad30)") (class "Default")
      (node (ref "U2") (pin "30") (pinfunction "DIFFIO_B6P_30") (pintype "bidirectional"))
    )
    (net (code "81") (name "unconnected-(U2B-DIFFIO_L1N-Pad1)") (class "Default")
      (node (ref "U2") (pin "1") (pinfunction "DIFFIO_L1N_1") (pintype "bidirectional"))
    )
    (net (code "82") (name "unconnected-(U2B-DIFFIO_L1P-Pad64)") (class "Default")
      (node (ref "U2") (pin "64") (pinfunction "DIFFIO_L1P_64") (pintype "bidirectional"))
    )
    (net (code "83") (name "unconnected-(U2B-DIFFIO_L2N-Pad4)") (class "Default")
      (node (ref "U2") (pin "4") (pinfunction "DIFFIO_L2N_4") (pintype "bidirectional"))
    )
    (net (code "84") (name "unconnected-(U2B-DIFFIO_L2P-Pad3)") (class "Default")
      (node (ref "U2") (pin "3") (pinfunction "DIFFIO_L2P_3") (pintype "bidirectional"))
    )
    (net (code "85") (name "unconnected-(U2B-DIFFIO_R1P-Pad47)") (class "Default")
      (node (ref "U2") (pin "47") (pinfunction "DIFFIO_R1P_47") (pintype "bidirectional"))
    )
    (net (code "86") (name "unconnected-(U2B-DIFFIO_R3N-Pad36)") (class "Default")
      (node (ref "U2") (pin "36") (pinfunction "DIFFIO_R3N_36") (pintype "bidirectional"))
    )
    (net (code "87") (name "unconnected-(U2B-DIFFIO_R3P-Pad37)") (class "Default")
      (node (ref "U2") (pin "37") (pinfunction "DIFFIO_R3P_37") (pintype "bidirectional"))
    )
    (net (code "88") (name "unconnected-(U2B-DIFFIO_T1N-Pad61)") (class "Default")
      (node (ref "U2") (pin "61") (pinfunction "DIFFIO_T1N_61") (pintype "bidirectional"))
    )
    (net (code "89") (name "unconnected-(U2B-DIFFIO_T1P-Pad63)") (class "Default")
      (node (ref "U2") (pin "63") (pinfunction "DIFFIO_T1P_63") (pintype "bidirectional"))
    )
    (net (code "90") (name "unconnected-(U2B-DIFFIO_T2N-Pad59)") (class "Default")
      (node (ref "U2") (pin "59") (pinfunction "DIFFIO_T2N_59") (pintype "bidirectional"))
    )
    (net (code "91") (name "unconnected-(U2B-DIFFIO_T2P-Pad60)") (class "Default")
      (node (ref "U2") (pin "60") (pinfunction "DIFFIO_T2P_60") (pintype "bidirectional"))
    )
    (net (code "92") (name "unconnected-(U2B-DIFFIO_T3N-Pad56)") (class "Default")
      (node (ref "U2") (pin "56") (pinfunction "DIFFIO_T3N_56") (pintype "bidirectional"))
    )
    (net (code "93") (name "unconnected-(U2B-DIFFIO_T3P-Pad58)") (class "Default")
      (node (ref "U2") (pin "58") (pinfunction "DIFFIO_T3P_58") (pintype "bidirectional"))
    )
    (net (code "94") (name "unconnected-(U2B-DIFFIO_T4N-Pad54)") (class "Default")
      (node (ref "U2") (pin "54") (pinfunction "DIFFIO_T4N_54") (pintype "bidirectional"))
    )
    (net (code "95") (name "unconnected-(U2B-DIFFIO_T4P-Pad55)") (class "Default")
      (node (ref "U2") (pin "55") (pinfunction "DIFFIO_T4P_55") (pintype "bidirectional"))
    )
    (net (code "96") (name "unconnected-(U2B-DIFFIO_T5N-Pad52)") (class "Default")
      (node (ref "U2") (pin "52") (pinfunction "DIFFIO_T5N_52") (pintype "bidirectional"))
    )
    (net (code "97") (name "unconnected-(U2B-DIFFIO_T5P-Pad53)") (class "Default")
      (node (ref "U2") (pin "53") (pinfunction "DIFFIO_T5P_53") (pintype "bidirectional"))
    )
  )
)
